# Sheet1.net
KiCad netlist of a schematic drawn in Altium Designer
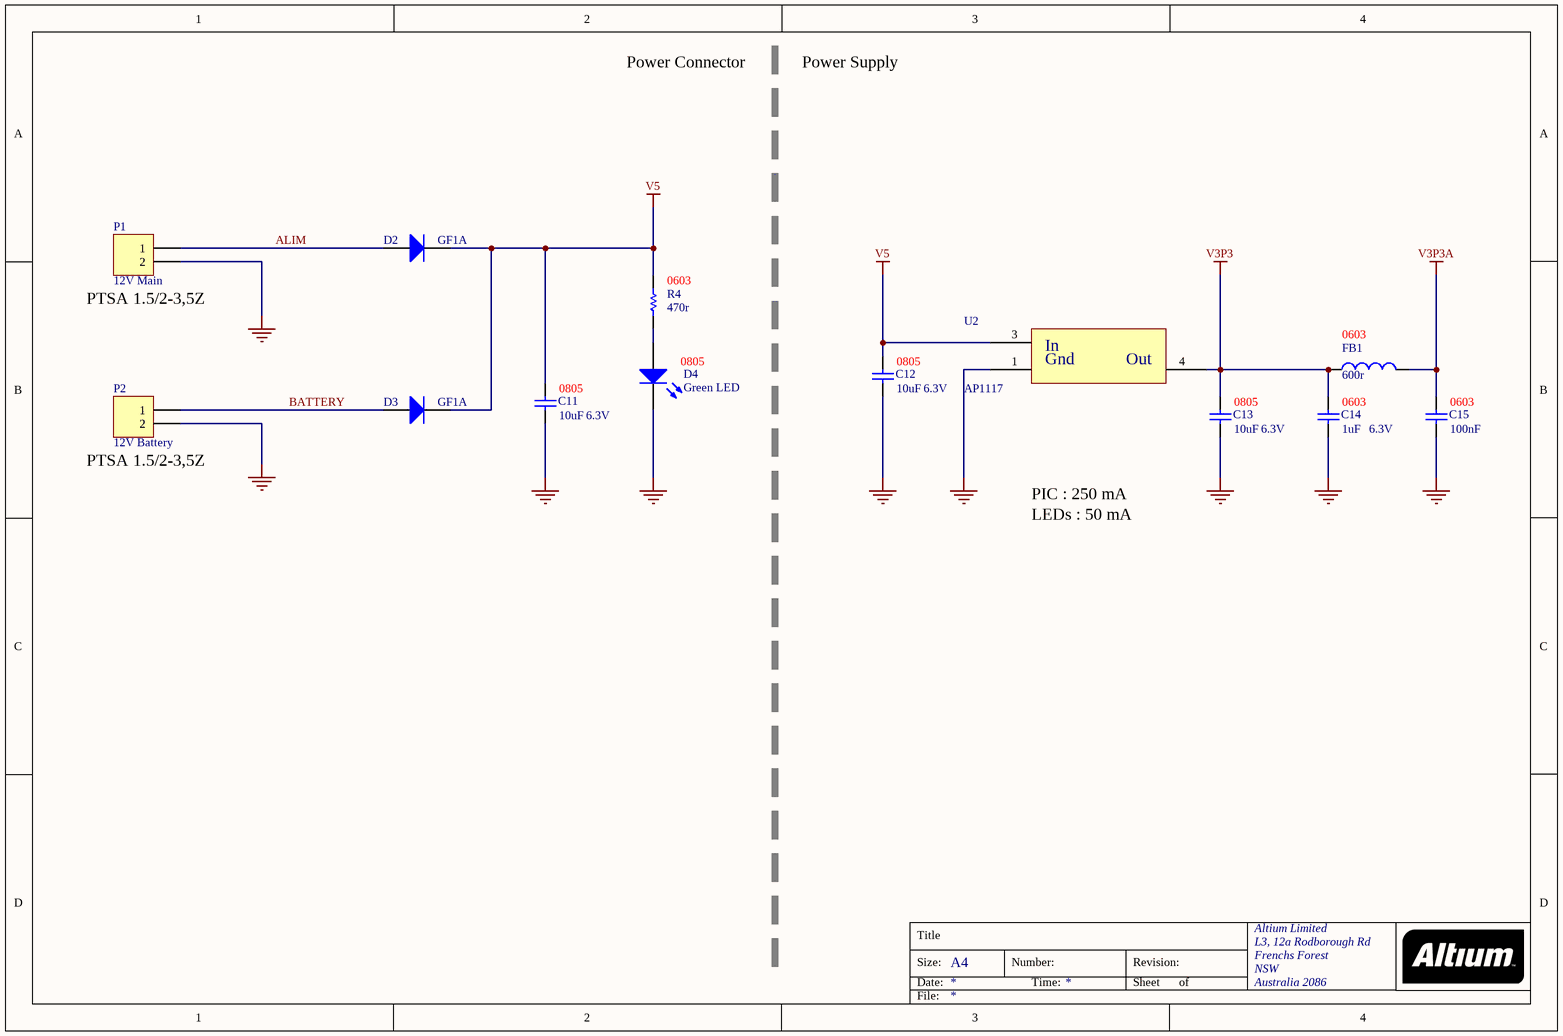
[diagram p0: Sheet1.SchDoc]

(export (version "E")
  (design (tool "Eeschema 10.0.6"))
  (components
    (comp (ref "C11")
      (value "6.3V")
      (footprint "CAPC2012N")
      (description "Capacitor")
      (fields (field (name "ALTIUM_VALUE") "10uF") (field (name "PUBLISHER") "Altium Limited"))
      (libsource (lib "Miscellaneous Devices") (part "Cap"))
    )
    (comp (ref "C12")
      (value "6.3V")
      (footprint "CAPC2012N")
      (description "Capacitor")
      (fields (field (name "ALTIUM_VALUE") "10uF") (field (name "PUBLISHER") "Altium Limited"))
      (libsource (lib "Miscellaneous Devices") (part "Cap"))
    )
    (comp (ref "C13")
      (value "6.3V")
      (footprint "CAPC2012N")
      (description "Capacitor")
      (fields (field (name "ALTIUM_VALUE") "10uF") (field (name "PUBLISHER") "Altium Limited"))
      (libsource (lib "Miscellaneous Devices") (part "Cap"))
    )
    (comp (ref "C14")
      (value "6.3V")
      (footprint "CAPC1608N")
      (description "Capacitor")
      (fields (field (name "ALTIUM_VALUE") "1uF") (field (name "PUBLISHER") "Altium Limited"))
      (libsource (lib "Miscellaneous Devices") (part "Cap"))
    )
    (comp (ref "C15")
      (value "100nF")
      (footprint "CAPC1608N")
      (description "Capacitor")
      (fields (field (name "Comment") "6.3V") (field (name "PUBLISHER") "Altium Limited"))
      (libsource (lib "Miscellaneous Devices") (part "Cap"))
    )
    (comp (ref "D2")
      (value "GF1A")
      (footprint "GF1A Diode")
      (description "Default Diode")
      (fields (field (name "PUBLISHER") "Altium Limited"))
      (libsource (lib "Miscellaneous Devices") (part "Diode"))
    )
    (comp (ref "D3")
      (value "GF1A")
      (footprint "GF1A Diode")
      (description "Default Diode")
      (fields (field (name "PUBLISHER") "Altium Limited"))
      (libsource (lib "Miscellaneous Devices") (part "Diode"))
    )
    (comp (ref "D4")
      (value "Green LED")
      (footprint "LED 0805N")
      (description "Typical INFRARED GaAs LED")
      (fields (field (name "PUBLISHER") "Altium Limited"))
      (libsource (lib "Miscellaneous Devices") (part "LED0"))
    )
    (comp (ref "FB1")
      (value "600r")
      (footprint "INDC1608AN")
      (description "Inductor")
      (fields (field (name "PUBLISHER") "Altium Limited"))
      (libsource (lib "Miscellaneous Devices") (part "Inductor"))
    )
    (comp (ref "P1")
      (value "12V Main")
      (footprint "PHOENIX_1985195")
      (description "Header, 2-Pin, Right Angle")
      (fields (field (name "PUBLISHER") "Altium Limited"))
      (libsource (lib "Miscellaneous Connectors") (part "Header 2H"))
    )
    (comp (ref "P2")
      (value "12V Battery")
      (footprint "PHOENIX_1985195")
      (description "Header, 2-Pin, Right Angle")
      (fields (field (name "PUBLISHER") "Altium Limited"))
      (libsource (lib "Miscellaneous Connectors") (part "Header 2H"))
    )
    (comp (ref "R4")
      (value "470r")
      (footprint "RESC1608N")
      (description "Resistor")
      (fields (field (name "Comment") "Res1") (field (name "PUBLISHER") "Altium Limited"))
      (libsource (lib "Miscellaneous Devices") (part "Res1"))
    )
    (comp (ref "U2") (value "AP1117") (footprint "TD03B_N") (libsource (lib "SchlibNOUS") (part "AP1117")))
  )
  (nets
    (net (code "1") (name "/ALIM") (class "Default")
      (node (ref "D2") (pin "1") (pinfunction "A_1") (pintype "passive"))
      (node (ref "P1") (pin "1") (pinfunction "1_1") (pintype "passive"))
    )
    (net (code "2") (name "/BATTERY") (class "Default")
      (node (ref "D3") (pin "1") (pinfunction "A_1") (pintype "passive"))
      (node (ref "P2") (pin "1") (pinfunction "1_1") (pintype "passive"))
    )
    (net (code "3") (name "GND") (class "Default")
      (node (ref "C11") (pin "1") (pinfunction "1_1") (pintype "passive"))
      (node (ref "C12") (pin "1") (pinfunction "1_1") (pintype "passive"))
      (node (ref "C13") (pin "1") (pinfunction "1_1") (pintype "passive"))
      (node (ref "C14") (pin "1") (pinfunction "1_1") (pintype "passive"))
      (node (ref "C15") (pin "1") (pinfunction "1_1") (pintype "passive"))
      (node (ref "D4") (pin "2") (pinfunction "K_2") (pintype "passive"))
      (node (ref "P1") (pin "2") (pinfunction "2_2") (pintype "passive"))
      (node (ref "P2") (pin "2") (pinfunction "2_2") (pintype "passive"))
      (node (ref "U2") (pin "1") (pinfunction "1_1") (pintype "passive"))
    )
    (net (code "4") (name "Net-(D4-A)") (class "Default")
      (node (ref "D4") (pin "1") (pinfunction "A_1") (pintype "passive"))
      (node (ref "R4") (pin "1") (pinfunction "1_1") (pintype "passive"))
    )
    (net (code "5") (name "V3P3") (class "Default")
      (node (ref "C13") (pin "2") (pinfunction "2_2") (pintype "passive"))
      (node (ref "C14") (pin "2") (pinfunction "2_2") (pintype "passive"))
      (node (ref "FB1") (pin "1") (pinfunction "1_1") (pintype "passive"))
      (node (ref "U2") (pin "4") (pinfunction "4_4") (pintype "passive"))
    )
    (net (code "6") (name "V3P3A") (class "Default")
      (node (ref "C15") (pin "2") (pinfunction "2_2") (pintype "passive"))
      (node (ref "FB1") (pin "2") (pinfunction "2_2") (pintype "passive"))
    )
    (net (code "7") (name "V5") (class "Default")
      (node (ref "C11") (pin "2") (pinfunction "2_2") (pintype "passive"))
      (node (ref "C12") (pin "2") (pinfunction "2_2") (pintype "passive"))
      (node (ref "D2") (pin "2") (pinfunction "K_2") (pintype "passive"))
      (node (ref "D3") (pin "2") (pinfunction "K_2") (pintype "passive"))
      (node (ref "R4") (pin "2") (pinfunction "2_2") (pintype "passive"))
      (node (ref "U2") (pin "3") (pinfunction "3_3") (pintype "passive"))
    )
  )
)
